# GatesDriver.net
KiCad netlist of a schematic drawn in Altium Designer
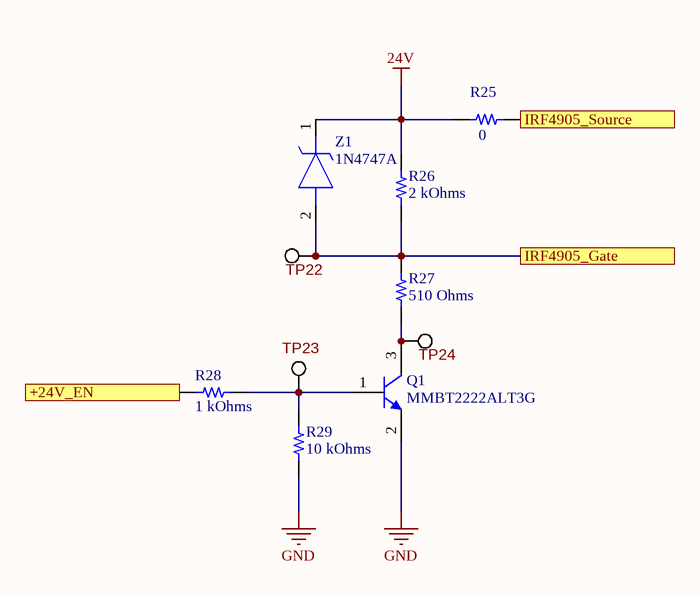
[diagram p0: GatesDriver.SchDoc]

(export (version "E")
  (design (tool "Eeschema 10.0.6"))
  (components
    (comp (ref "Q1")
      (value "MMBT2222ALT3G")
      (footprint "ON SEMI SOT-23-3")
      (description "TRANS NPN 40V 0.6A SOT-23")
      (fields (field (name "MANUFACTURER") "ON Semiconductor"))
      (libsource (lib "Celestial Altium Library - altium_library") (part "ON SEMI NPN SOT-23-3"))
    )
    (comp (ref "R25")
      (value "0")
      (footprint "RES 0805_2012")
      (description "RES 0 OHM JUMPER 0805")
      (fields
        (field (name "PART NUMBER") "TLRZ2ATTD")
        (field (name "MANUFACTURER") "KOA Speer Electronics, Inc.")
      )
      (libsource (lib "Celestial Altium Library - altium_library") (part "Resistor"))
    )
    (comp (ref "R26")
      (value "2 kOhms")
      (footprint "RES 0805_2012")
      (description "RES SMD 2K OHM 1% 0.4W 0805")
      (fields (field (name "PART NUMBER") "RCS08052K00FKEA") (field (name "MANUFACTURER") "Vishay Dale"))
      (libsource (lib "Celestial Altium Library - altium_library") (part "Resistor"))
    )
    (comp (ref "R27")
      (value "510 Ohms")
      (footprint "RES 0805_2012")
      (description "RES 510 OHM 0.1% 1/8W 0805")
      (fields
        (field (name "PART NUMBER") "ERA-6APB511V")
        (field (name "MANUFACTURER") "Panasonic Electronic Components")
      )
      (libsource (lib "Celestial Altium Library - altium_library") (part "Resistor"))
    )
    (comp (ref "R28")
      (value "1 kOhms")
      (footprint "RES 0805_2012")
      (description "RES 1K OHM 0.1% 1/10W 0805")
      (fields
        (field (name "PART NUMBER") "RNCS0805BKE1K00")
        (field (name "MANUFACTURER") "Stackpole Electronics Inc")
      )
      (libsource (lib "Celestial Altium Library - altium_library") (part "Resistor"))
    )
    (comp (ref "R29")
      (value "10 kOhms")
      (footprint "RES 0805_2012")
      (description "RES 10K OHM 0.1% 1/10W 0805")
      (fields
        (field (name "PART NUMBER") "RNCS0805BKE10K0")
        (field (name "MANUFACTURER") "Stackpole Electronics Inc")
      )
      (libsource (lib "Celestial Altium Library - altium_library") (part "Resistor"))
    )
    (comp (ref "TP22")
      (value "PAD-1.1mm")
      (footprint "PAD-1.1mm")
      (description "1.1mm Pad for Plug-In or Receptacle")
      (fields (field (name "MANUFACTURER") "NONE"))
      (libsource (lib "misc") (part "PAD-1.1mm"))
    )
    (comp (ref "TP23")
      (value "PAD-1.1mm")
      (footprint "PAD-1.1mm")
      (description "1.1mm Pad for Plug-In or Receptacle")
      (fields (field (name "MANUFACTURER") "NONE"))
      (libsource (lib "misc") (part "PAD-1.1mm"))
    )
    (comp (ref "TP24")
      (value "PAD-1.1mm")
      (footprint "PAD-1.1mm")
      (description "1.1mm Pad for Plug-In or Receptacle")
      (fields (field (name "MANUFACTURER") "NONE"))
      (libsource (lib "misc") (part "PAD-1.1mm"))
    )
    (comp (ref "Z1")
      (value "1N4747A")
      (footprint "SamacSys:DIOAD1310W86L370D235")
      (description "Zener Diode")
      (libsource (lib "*") (part "1N4747A"))
    )
  )
  (nets
    (net (code "1") (name "/+24V_EN") (class "Default")
      (node (ref "R28") (pin "1") (pinfunction "1_1") (pintype "passive"))
    )
    (net (code "2") (name "/IRF4905_Gate") (class "Default")
      (node (ref "R26") (pin "1") (pinfunction "1_1") (pintype "passive"))
      (node (ref "R27") (pin "2") (pinfunction "2_2") (pintype "passive"))
      (node (ref "TP22") (pin "1") (pintype "passive"))
      (node (ref "Z1") (pin "2") (pinfunction "A_2") (pintype "passive"))
    )
    (net (code "3") (name "/IRF4905_Source") (class "Default")
      (node (ref "R25") (pin "2") (pinfunction "2_2") (pintype "passive"))
    )
    (net (code "4") (name "24V") (class "Default")
      (node (ref "R25") (pin "1") (pinfunction "1_1") (pintype "passive"))
      (node (ref "R26") (pin "2") (pinfunction "2_2") (pintype "passive"))
      (node (ref "Z1") (pin "1") (pinfunction "K_1") (pintype "passive"))
    )
    (net (code "5") (name "GND") (class "Default")
      (node (ref "Q1") (pin "2") (pinfunction "E_2") (pintype "passive"))
      (node (ref "R29") (pin "1") (pinfunction "1_1") (pintype "passive"))
    )
    (net (code "6") (name "Net-(Q1-B)") (class "Default")
      (node (ref "Q1") (pin "1") (pinfunction "B_1") (pintype "passive"))
      (node (ref "R28") (pin "2") (pinfunction "2_2") (pintype "passive"))
      (node (ref "R29") (pin "2") (pinfunction "2_2") (pintype "passive"))
      (node (ref "TP23") (pin "1") (pintype "passive"))
    )
    (net (code "7") (name "Net-(Q1-C)") (class "Default")
      (node (ref "Q1") (pin "3") (pinfunction "C_3") (pintype "passive"))
      (node (ref "R27") (pin "1") (pinfunction "1_1") (pintype "passive"))
      (node (ref "TP24") (pin "1") (pintype "passive"))
    )
  )
)
